# Pin-Filters.net
KiCad netlist of a schematic drawn in Altium Designer
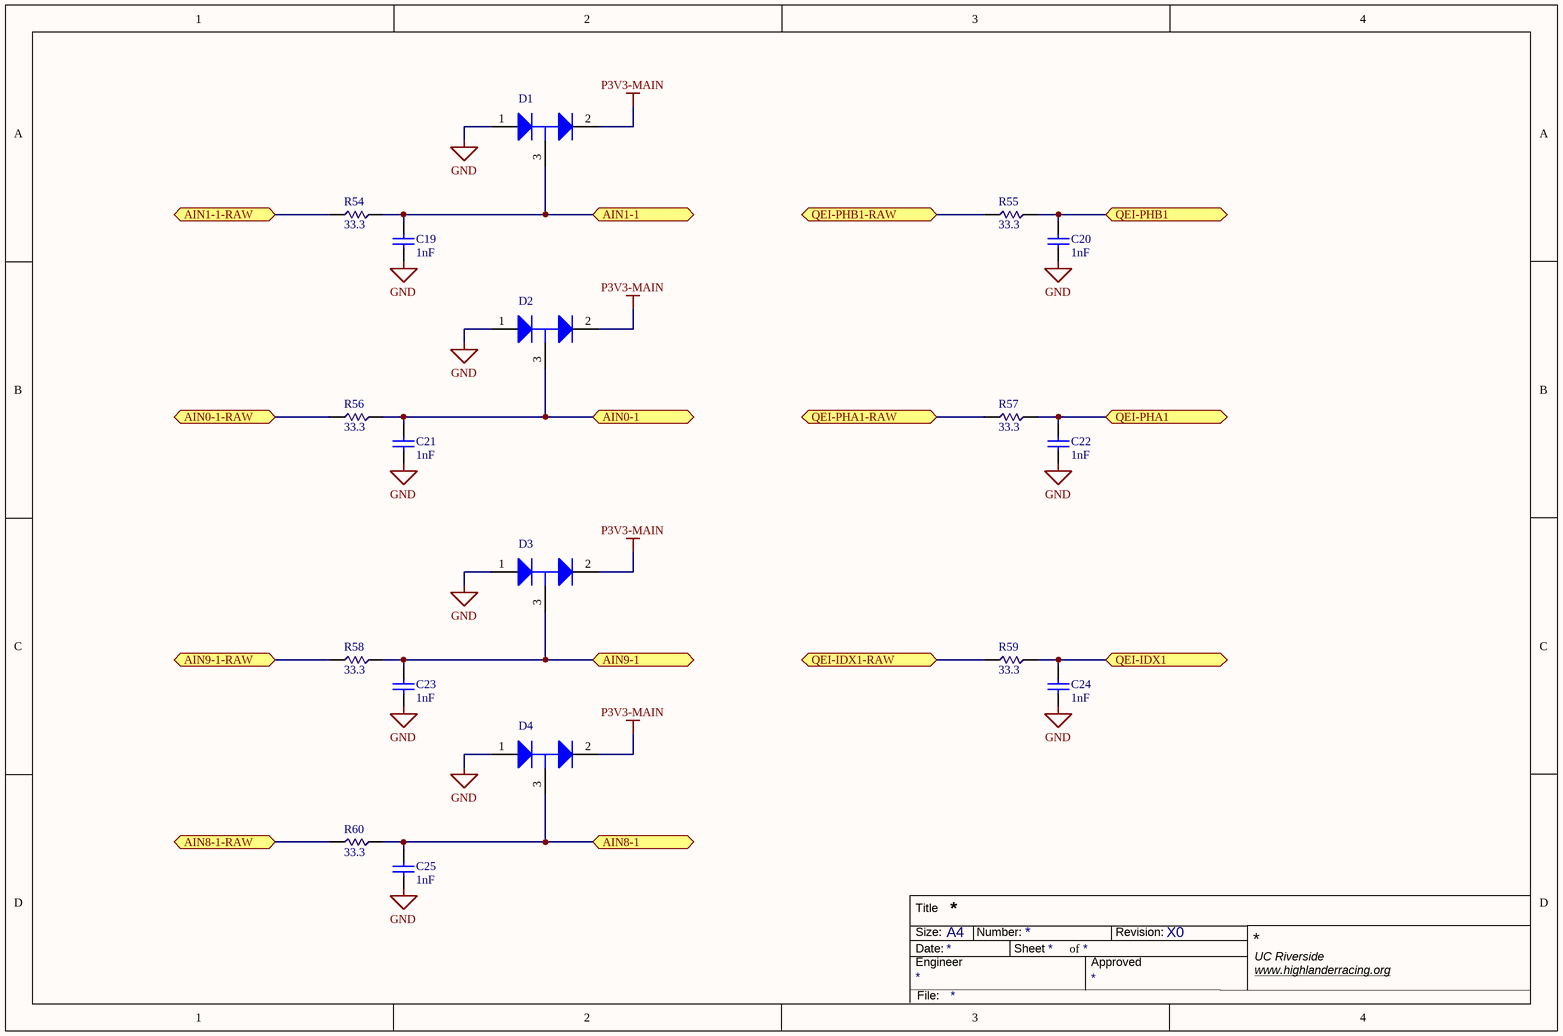
[diagram p0: Pin-Filters.SchDoc]

(export (version "E")
  (design (tool "Eeschema 10.0.6"))
  (components
    (comp (ref "C19")
      (value "1nF")
      (footprint "FOOTPRINT-0805-GEN")
      (description "Capacitor")
      (fields (field (name "Comment") "Capacitor-Generic-0805") (field (name "PUBLISHER") "Altium Limited"))
      (libsource (lib "HR-Master-Integrated") (part "Capacitor-Generic-0805"))
    )
    (comp (ref "C20")
      (value "1nF")
      (footprint "FOOTPRINT-0805-GEN")
      (description "Capacitor")
      (fields (field (name "Comment") "Capacitor-Generic-0805") (field (name "PUBLISHER") "Altium Limited"))
      (libsource (lib "HR-Master-Integrated") (part "Capacitor-Generic-0805"))
    )
    (comp (ref "C21")
      (value "1nF")
      (footprint "FOOTPRINT-0805-GEN")
      (description "Capacitor")
      (fields (field (name "Comment") "Capacitor-Generic-0805") (field (name "PUBLISHER") "Altium Limited"))
      (libsource (lib "HR-Master-Integrated") (part "Capacitor-Generic-0805"))
    )
    (comp (ref "C22")
      (value "1nF")
      (footprint "FOOTPRINT-0805-GEN")
      (description "Capacitor")
      (fields (field (name "Comment") "Capacitor-Generic-0805") (field (name "PUBLISHER") "Altium Limited"))
      (libsource (lib "HR-Master-Integrated") (part "Capacitor-Generic-0805"))
    )
    (comp (ref "C23")
      (value "1nF")
      (footprint "FOOTPRINT-0805-GEN")
      (description "Capacitor")
      (fields (field (name "Comment") "Capacitor-Generic-0805") (field (name "PUBLISHER") "Altium Limited"))
      (libsource (lib "HR-Master-Integrated") (part "Capacitor-Generic-0805"))
    )
    (comp (ref "C24")
      (value "1nF")
      (footprint "FOOTPRINT-0805-GEN")
      (description "Capacitor")
      (fields (field (name "Comment") "Capacitor-Generic-0805") (field (name "PUBLISHER") "Altium Limited"))
      (libsource (lib "HR-Master-Integrated") (part "Capacitor-Generic-0805"))
    )
    (comp (ref "C25")
      (value "1nF")
      (footprint "FOOTPRINT-0805-GEN")
      (description "Capacitor")
      (fields (field (name "Comment") "Capacitor-Generic-0805") (field (name "PUBLISHER") "Altium Limited"))
      (libsource (lib "HR-Master-Integrated") (part "Capacitor-Generic-0805"))
    )
    (comp (ref "D1")
      (value "BAT54SLT1G")
      (footprint "FOOTPRINT-ONSC-SOT23-1A2KA3K")
      (description "Dual Series Schottky Barrier Diodes, 3-Pin SOT-23, Pb-Free, Tape and Reel")
      (fields (field (name "MANUFACTURER") "On Semiconductor"))
      (libsource (lib "HR-Master-Integrated") (part "Diode-ONSC-BAT54S"))
    )
    (comp (ref "D2")
      (value "BAT54SLT1G")
      (footprint "FOOTPRINT-ONSC-SOT23-1A2KA3K")
      (description "Dual Series Schottky Barrier Diodes, 3-Pin SOT-23, Pb-Free, Tape and Reel")
      (fields (field (name "MANUFACTURER") "On Semiconductor"))
      (libsource (lib "HR-Master-Integrated") (part "Diode-ONSC-BAT54S"))
    )
    (comp (ref "D3")
      (value "BAT54SLT1G")
      (footprint "FOOTPRINT-ONSC-SOT23-1A2KA3K")
      (description "Dual Series Schottky Barrier Diodes, 3-Pin SOT-23, Pb-Free, Tape and Reel")
      (fields (field (name "MANUFACTURER") "On Semiconductor"))
      (libsource (lib "HR-Master-Integrated") (part "Diode-ONSC-BAT54S"))
    )
    (comp (ref "D4")
      (value "BAT54SLT1G")
      (footprint "FOOTPRINT-ONSC-SOT23-1A2KA3K")
      (description "Dual Series Schottky Barrier Diodes, 3-Pin SOT-23, Pb-Free, Tape and Reel")
      (fields (field (name "MANUFACTURER") "On Semiconductor"))
      (libsource (lib "HR-Master-Integrated") (part "Diode-ONSC-BAT54S"))
    )
    (comp (ref "R54")
      (value "33.3")
      (footprint "FOOTPRINT-0805-GEN")
      (description "1/8 Watt Surface Mount Resistor")
      (fields (field (name "Comment") "SMC"))
      (libsource (lib "HR-Master-Integrated") (part "Resistor-Generic-0805-2012"))
    )
    (comp (ref "R55")
      (value "33.3")
      (footprint "FOOTPRINT-0805-GEN")
      (description "1/8 Watt Surface Mount Resistor")
      (fields (field (name "Comment") "SMC"))
      (libsource (lib "HR-Master-Integrated") (part "Resistor-Generic-0805-2012"))
    )
    (comp (ref "R56")
      (value "33.3")
      (footprint "FOOTPRINT-0805-GEN")
      (description "1/8 Watt Surface Mount Resistor")
      (fields (field (name "Comment") "SMC"))
      (libsource (lib "HR-Master-Integrated") (part "Resistor-Generic-0805-2012"))
    )
    (comp (ref "R57")
      (value "33.3")
      (footprint "FOOTPRINT-0805-GEN")
      (description "1/8 Watt Surface Mount Resistor")
      (fields (field (name "Comment") "SMC"))
      (libsource (lib "HR-Master-Integrated") (part "Resistor-Generic-0805-2012"))
    )
    (comp (ref "R58")
      (value "33.3")
      (footprint "FOOTPRINT-0805-GEN")
      (description "1/8 Watt Surface Mount Resistor")
      (fields (field (name "Comment") "SMC"))
      (libsource (lib "HR-Master-Integrated") (part "Resistor-Generic-0805-2012"))
    )
    (comp (ref "R59")
      (value "33.3")
      (footprint "FOOTPRINT-0805-GEN")
      (description "1/8 Watt Surface Mount Resistor")
      (fields (field (name "Comment") "SMC"))
      (libsource (lib "HR-Master-Integrated") (part "Resistor-Generic-0805-2012"))
    )
    (comp (ref "R60")
      (value "33.3")
      (footprint "FOOTPRINT-0805-GEN")
      (description "1/8 Watt Surface Mount Resistor")
      (fields (field (name "Comment") "SMC"))
      (libsource (lib "HR-Master-Integrated") (part "Resistor-Generic-0805-2012"))
    )
  )
  (nets
    (net (code "1") (name "/AIN0-1") (class "Default")
      (node (ref "C21") (pin "2") (pinfunction "2_2") (pintype "passive"))
      (node (ref "D2") (pin "3") (pinfunction "K/A_3") (pintype "passive"))
      (node (ref "R56") (pin "2") (pinfunction "2_2") (pintype "passive"))
    )
    (net (code "2") (name "/AIN0-1-RAW") (class "Default")
      (node (ref "R56") (pin "1") (pinfunction "1_1") (pintype "passive"))
    )
    (net (code "3") (name "/AIN1-1") (class "Default")
      (node (ref "C19") (pin "2") (pinfunction "2_2") (pintype "passive"))
      (node (ref "D1") (pin "3") (pinfunction "K/A_3") (pintype "passive"))
      (node (ref "R54") (pin "2") (pinfunction "2_2") (pintype "passive"))
    )
    (net (code "4") (name "/AIN1-1-RAW") (class "Default")
      (node (ref "R54") (pin "1") (pinfunction "1_1") (pintype "passive"))
    )
    (net (code "5") (name "/AIN8-1") (class "Default")
      (node (ref "C25") (pin "2") (pinfunction "2_2") (pintype "passive"))
      (node (ref "D4") (pin "3") (pinfunction "K/A_3") (pintype "passive"))
      (node (ref "R60") (pin "2") (pinfunction "2_2") (pintype "passive"))
    )
    (net (code "6") (name "/AIN8-1-RAW") (class "Default")
      (node (ref "R60") (pin "1") (pinfunction "1_1") (pintype "passive"))
    )
    (net (code "7") (name "/AIN9-1") (class "Default")
      (node (ref "C23") (pin "2") (pinfunction "2_2") (pintype "passive"))
      (node (ref "D3") (pin "3") (pinfunction "K/A_3") (pintype "passive"))
      (node (ref "R58") (pin "2") (pinfunction "2_2") (pintype "passive"))
    )
    (net (code "8") (name "/AIN9-1-RAW") (class "Default")
      (node (ref "R58") (pin "1") (pinfunction "1_1") (pintype "passive"))
    )
    (net (code "9") (name "/QEI-IDX1") (class "Default")
      (node (ref "C24") (pin "2") (pinfunction "2_2") (pintype "passive"))
      (node (ref "R59") (pin "2") (pinfunction "2_2") (pintype "passive"))
    )
    (net (code "10") (name "/QEI-IDX1-RAW") (class "Default")
      (node (ref "R59") (pin "1") (pinfunction "1_1") (pintype "passive"))
    )
    (net (code "11") (name "/QEI-PHA1") (class "Default")
      (node (ref "C22") (pin "2") (pinfunction "2_2") (pintype "passive"))
      (node (ref "R57") (pin "2") (pinfunction "2_2") (pintype "passive"))
    )
    (net (code "12") (name "/QEI-PHA1-RAW") (class "Default")
      (node (ref "R57") (pin "1") (pinfunction "1_1") (pintype "passive"))
    )
    (net (code "13") (name "/QEI-PHB1") (class "Default")
      (node (ref "C20") (pin "2") (pinfunction "2_2") (pintype "passive"))
      (node (ref "R55") (pin "2") (pinfunction "2_2") (pintype "passive"))
    )
    (net (code "14") (name "/QEI-PHB1-RAW") (class "Default")
      (node (ref "R55") (pin "1") (pinfunction "1_1") (pintype "passive"))
    )
    (net (code "15") (name "GND") (class "Default")
      (node (ref "C19") (pin "1") (pinfunction "1_1") (pintype "passive"))
      (node (ref "C20") (pin "1") (pinfunction "1_1") (pintype "passive"))
      (node (ref "C21") (pin "1") (pinfunction "1_1") (pintype "passive"))
      (node (ref "C22") (pin "1") (pinfunction "1_1") (pintype "passive"))
      (node (ref "C23") (pin "1") (pinfunction "1_1") (pintype "passive"))
      (node (ref "C24") (pin "1") (pinfunction "1_1") (pintype "passive"))
      (node (ref "C25") (pin "1") (pinfunction "1_1") (pintype "passive"))
      (node (ref "D1") (pin "1") (pinfunction "A_1") (pintype "passive"))
      (node (ref "D2") (pin "1") (pinfunction "A_1") (pintype "passive"))
      (node (ref "D3") (pin "1") (pinfunction "A_1") (pintype "passive"))
      (node (ref "D4") (pin "1") (pinfunction "A_1") (pintype "passive"))
    )
    (net (code "16") (name "P3V3-MAIN") (class "Default")
      (node (ref "D1") (pin "2") (pinfunction "K_2") (pintype "passive"))
      (node (ref "D2") (pin "2") (pinfunction "K_2") (pintype "passive"))
      (node (ref "D3") (pin "2") (pinfunction "K_2") (pintype "passive"))
      (node (ref "D4") (pin "2") (pinfunction "K_2") (pintype "passive"))
    )
  )
)
